# led.net
KiCad netlist of a schematic drawn in EAGLE
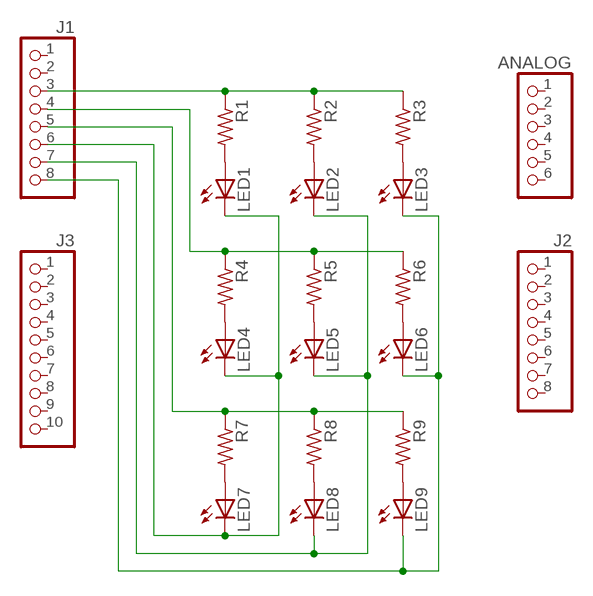
[diagram p0: schematic, sheet 1]

(export (version "E")
  (design (tool "Eeschema 10.0.6"))
  (components
    (comp (ref "ANALOG")
      (value "PINHD-1X6")
      (footprint "eagle-import:1X06")
      (libsource (lib "eagle-import") (part "PINHD-1X6"))
    )
    (comp (ref "J1")
      (value "PINHD-1X8TH")
      (footprint "eagle-import:1X08-TH")
      (libsource (lib "eagle-import") (part "PINHD-1X8TH"))
    )
    (comp (ref "J2")
      (value "PINHD-1X8TH")
      (footprint "eagle-import:1X08-TH")
      (libsource (lib "eagle-import") (part "PINHD-1X8TH"))
    )
    (comp (ref "J3")
      (value "PINHD-1X10TH")
      (footprint "eagle-import:1X10-TH")
      (libsource (lib "eagle-import") (part "PINHD-1X10TH"))
    )
    (comp (ref "LED1")
      (value "LED3MM")
      (footprint "eagle-import:LED3MM")
      (libsource (lib "eagle-import") (part "LED3MM"))
    )
    (comp (ref "LED2")
      (value "LED3MM")
      (footprint "eagle-import:LED3MM")
      (libsource (lib "eagle-import") (part "LED3MM"))
    )
    (comp (ref "LED3")
      (value "LED3MM")
      (footprint "eagle-import:LED3MM")
      (libsource (lib "eagle-import") (part "LED3MM"))
    )
    (comp (ref "LED4")
      (value "LED3MM")
      (footprint "eagle-import:LED3MM")
      (libsource (lib "eagle-import") (part "LED3MM"))
    )
    (comp (ref "LED5")
      (value "LED3MM")
      (footprint "eagle-import:LED3MM")
      (libsource (lib "eagle-import") (part "LED3MM"))
    )
    (comp (ref "LED6")
      (value "LED3MM")
      (footprint "eagle-import:LED3MM")
      (libsource (lib "eagle-import") (part "LED3MM"))
    )
    (comp (ref "LED7")
      (value "LED3MM")
      (footprint "eagle-import:LED3MM")
      (libsource (lib "eagle-import") (part "LED3MM"))
    )
    (comp (ref "LED8")
      (value "LED3MM")
      (footprint "eagle-import:LED3MM")
      (libsource (lib "eagle-import") (part "LED3MM"))
    )
    (comp (ref "LED9")
      (value "LED3MM")
      (footprint "eagle-import:LED3MM")
      (libsource (lib "eagle-import") (part "LED3MM"))
    )
    (comp (ref "R1")
      (value "R-US_0207/10")
      (footprint "eagle-import:0207_10")
      (libsource (lib "eagle-import") (part "R-US_0207/10"))
    )
    (comp (ref "R2")
      (value "R-US_0207/10")
      (footprint "eagle-import:0207_10")
      (libsource (lib "eagle-import") (part "R-US_0207/10"))
    )
    (comp (ref "R3")
      (value "R-US_0207/10")
      (footprint "eagle-import:0207_10")
      (libsource (lib "eagle-import") (part "R-US_0207/10"))
    )
    (comp (ref "R4")
      (value "R-US_0207/10")
      (footprint "eagle-import:0207_10")
      (libsource (lib "eagle-import") (part "R-US_0207/10"))
    )
    (comp (ref "R5")
      (value "R-US_0207/10")
      (footprint "eagle-import:0207_10")
      (libsource (lib "eagle-import") (part "R-US_0207/10"))
    )
    (comp (ref "R6")
      (value "R-US_0207/10")
      (footprint "eagle-import:0207_10")
      (libsource (lib "eagle-import") (part "R-US_0207/10"))
    )
    (comp (ref "R7")
      (value "R-US_0207/10")
      (footprint "eagle-import:0207_10")
      (libsource (lib "eagle-import") (part "R-US_0207/10"))
    )
    (comp (ref "R8")
      (value "R-US_0207/10")
      (footprint "eagle-import:0207_10")
      (libsource (lib "eagle-import") (part "R-US_0207/10"))
    )
    (comp (ref "R9")
      (value "R-US_0207/10")
      (footprint "eagle-import:0207_10")
      (libsource (lib "eagle-import") (part "R-US_0207/10"))
    )
  )
  (nets
    (net (code "1") (name "Net-(J1-Pad3)") (class "Default")
      (node (ref "J1") (pin "3") (pinfunction "3_3") (pintype "passive"))
      (node (ref "R1") (pin "1") (pinfunction "1_1") (pintype "passive"))
      (node (ref "R2") (pin "1") (pinfunction "1_1") (pintype "passive"))
      (node (ref "R3") (pin "1") (pinfunction "1_1") (pintype "passive"))
    )
    (net (code "2") (name "Net-(J1-Pad4)") (class "Default")
      (node (ref "J1") (pin "4") (pinfunction "4_4") (pintype "passive"))
      (node (ref "R4") (pin "1") (pinfunction "1_1") (pintype "passive"))
      (node (ref "R5") (pin "1") (pinfunction "1_1") (pintype "passive"))
      (node (ref "R6") (pin "1") (pinfunction "1_1") (pintype "passive"))
    )
    (net (code "3") (name "Net-(J1-Pad5)") (class "Default")
      (node (ref "J1") (pin "5") (pinfunction "5_5") (pintype "passive"))
      (node (ref "R7") (pin "1") (pinfunction "1_1") (pintype "passive"))
      (node (ref "R8") (pin "1") (pinfunction "1_1") (pintype "passive"))
      (node (ref "R9") (pin "1") (pinfunction "1_1") (pintype "passive"))
    )
    (net (code "4") (name "Net-(LED1-C)") (class "Default")
      (node (ref "J1") (pin "6") (pinfunction "6_6") (pintype "passive"))
      (node (ref "LED1") (pin "K") (pinfunction "C_K") (pintype "passive"))
      (node (ref "LED4") (pin "K") (pinfunction "C_K") (pintype "passive"))
      (node (ref "LED7") (pin "K") (pinfunction "C_K") (pintype "passive"))
    )
    (net (code "5") (name "Net-(LED1-PadA)") (class "Default")
      (node (ref "LED1") (pin "A") (pinfunction "A_A") (pintype "passive"))
      (node (ref "R1") (pin "2") (pinfunction "2_2") (pintype "passive"))
    )
    (net (code "6") (name "Net-(LED2-C)") (class "Default")
      (node (ref "J1") (pin "7") (pinfunction "7_7") (pintype "passive"))
      (node (ref "LED2") (pin "K") (pinfunction "C_K") (pintype "passive"))
      (node (ref "LED5") (pin "K") (pinfunction "C_K") (pintype "passive"))
      (node (ref "LED8") (pin "K") (pinfunction "C_K") (pintype "passive"))
    )
    (net (code "7") (name "Net-(LED2-PadA)") (class "Default")
      (node (ref "LED2") (pin "A") (pinfunction "A_A") (pintype "passive"))
      (node (ref "R2") (pin "2") (pinfunction "2_2") (pintype "passive"))
    )
    (net (code "8") (name "Net-(LED3-C)") (class "Default")
      (node (ref "J1") (pin "8") (pinfunction "8_8") (pintype "passive"))
      (node (ref "LED3") (pin "K") (pinfunction "C_K") (pintype "passive"))
      (node (ref "LED6") (pin "K") (pinfunction "C_K") (pintype "passive"))
      (node (ref "LED9") (pin "K") (pinfunction "C_K") (pintype "passive"))
    )
    (net (code "9") (name "Net-(LED3-PadA)") (class "Default")
      (node (ref "LED3") (pin "A") (pinfunction "A_A") (pintype "passive"))
      (node (ref "R3") (pin "2") (pinfunction "2_2") (pintype "passive"))
    )
    (net (code "10") (name "Net-(LED4-PadA)") (class "Default")
      (node (ref "LED4") (pin "A") (pinfunction "A_A") (pintype "passive"))
      (node (ref "R4") (pin "2") (pinfunction "2_2") (pintype "passive"))
    )
    (net (code "11") (name "Net-(LED5-PadA)") (class "Default")
      (node (ref "LED5") (pin "A") (pinfunction "A_A") (pintype "passive"))
      (node (ref "R5") (pin "2") (pinfunction "2_2") (pintype "passive"))
    )
    (net (code "12") (name "Net-(LED6-PadA)") (class "Default")
      (node (ref "LED6") (pin "A") (pinfunction "A_A") (pintype "passive"))
      (node (ref "R6") (pin "2") (pinfunction "2_2") (pintype "passive"))
    )
    (net (code "13") (name "Net-(LED7-PadA)") (class "Default")
      (node (ref "LED7") (pin "A") (pinfunction "A_A") (pintype "passive"))
      (node (ref "R7") (pin "2") (pinfunction "2_2") (pintype "passive"))
    )
    (net (code "14") (name "Net-(LED8-PadA)") (class "Default")
      (node (ref "LED8") (pin "A") (pinfunction "A_A") (pintype "passive"))
      (node (ref "R8") (pin "2") (pinfunction "2_2") (pintype "passive"))
    )
    (net (code "15") (name "Net-(LED9-PadA)") (class "Default")
      (node (ref "LED9") (pin "A") (pinfunction "A_A") (pintype "passive"))
      (node (ref "R9") (pin "2") (pinfunction "2_2") (pintype "passive"))
    )
    (net (code "16") (name "unconnected-(ANALOG-Pad1)") (class "Default")
      (node (ref "ANALOG") (pin "1") (pinfunction "1_1") (pintype "passive"))
    )
    (net (code "17") (name "unconnected-(ANALOG-Pad2)") (class "Default")
      (node (ref "ANALOG") (pin "2") (pinfunction "2_2") (pintype "passive"))
    )
    (net (code "18") (name "unconnected-(ANALOG-Pad3)") (class "Default")
      (node (ref "ANALOG") (pin "3") (pinfunction "3_3") (pintype "passive"))
    )
    (net (code "19") (name "unconnected-(ANALOG-Pad4)") (class "Default")
      (node (ref "ANALOG") (pin "4") (pinfunction "4_4") (pintype "passive"))
    )
    (net (code "20") (name "unconnected-(ANALOG-Pad5)") (class "Default")
      (node (ref "ANALOG") (pin "5") (pinfunction "5_5") (pintype "passive"))
    )
    (net (code "21") (name "unconnected-(ANALOG-Pad6)") (class "Default")
      (node (ref "ANALOG") (pin "6") (pinfunction "6_6") (pintype "passive"))
    )
    (net (code "22") (name "unconnected-(J1-Pad1)") (class "Default")
      (node (ref "J1") (pin "1") (pinfunction "1_1") (pintype "passive"))
    )
    (net (code "23") (name "unconnected-(J1-Pad2)") (class "Default")
      (node (ref "J1") (pin "2") (pinfunction "2_2") (pintype "passive"))
    )
    (net (code "24") (name "unconnected-(J2-Pad1)") (class "Default")
      (node (ref "J2") (pin "1") (pinfunction "1_1") (pintype "passive"))
    )
    (net (code "25") (name "unconnected-(J2-Pad2)") (class "Default")
      (node (ref "J2") (pin "2") (pinfunction "2_2") (pintype "passive"))
    )
    (net (code "26") (name "unconnected-(J2-Pad3)") (class "Default")
      (node (ref "J2") (pin "3") (pinfunction "3_3") (pintype "passive"))
    )
    (net (code "27") (name "unconnected-(J2-Pad4)") (class "Default")
      (node (ref "J2") (pin "4") (pinfunction "4_4") (pintype "passive"))
    )
    (net (code "28") (name "unconnected-(J2-Pad5)") (class "Default")
      (node (ref "J2") (pin "5") (pinfunction "5_5") (pintype "passive"))
    )
    (net (code "29") (name "unconnected-(J2-Pad6)") (class "Default")
      (node (ref "J2") (pin "6") (pinfunction "6_6") (pintype "passive"))
    )
    (net (code "30") (name "unconnected-(J2-Pad7)") (class "Default")
      (node (ref "J2") (pin "7") (pinfunction "7_7") (pintype "passive"))
    )
    (net (code "31") (name "unconnected-(J2-Pad8)") (class "Default")
      (node (ref "J2") (pin "8") (pinfunction "8_8") (pintype "passive"))
    )
    (net (code "32") (name "unconnected-(J3-Pad1)") (class "Default")
      (node (ref "J3") (pin "1") (pinfunction "1_1") (pintype "passive"))
    )
    (net (code "33") (name "unconnected-(J3-Pad2)") (class "Default")
      (node (ref "J3") (pin "2") (pinfunction "2_2") (pintype "passive"))
    )
    (net (code "34") (name "unconnected-(J3-Pad3)") (class "Default")
      (node (ref "J3") (pin "3") (pinfunction "3_3") (pintype "passive"))
    )
    (net (code "35") (name "unconnected-(J3-Pad4)") (class "Default")
      (node (ref "J3") (pin "4") (pinfunction "4_4") (pintype "passive"))
    )
    (net (code "36") (name "unconnected-(J3-Pad5)") (class "Default")
      (node (ref "J3") (pin "5") (pinfunction "5_5") (pintype "passive"))
    )
    (net (code "37") (name "unconnected-(J3-Pad6)") (class "Default")
      (node (ref "J3") (pin "6") (pinfunction "6_6") (pintype "passive"))
    )
    (net (code "38") (name "unconnected-(J3-Pad7)") (class "Default")
      (node (ref "J3") (pin "7") (pinfunction "7_7") (pintype "passive"))
    )
    (net (code "39") (name "unconnected-(J3-Pad8)") (class "Default")
      (node (ref "J3") (pin "8") (pinfunction "8_8") (pintype "passive"))
    )
    (net (code "40") (name "unconnected-(J3-Pad9)") (class "Default")
      (node (ref "J3") (pin "9") (pinfunction "9_9") (pintype "passive"))
    )
    (net (code "41") (name "unconnected-(J3-Pad10)") (class "Default")
      (node (ref "J3") (pin "10") (pinfunction "10_10") (pintype "passive"))
    )
  )
)
